# Ethernet.net
KiCad netlist of a schematic drawn in Altium Designer
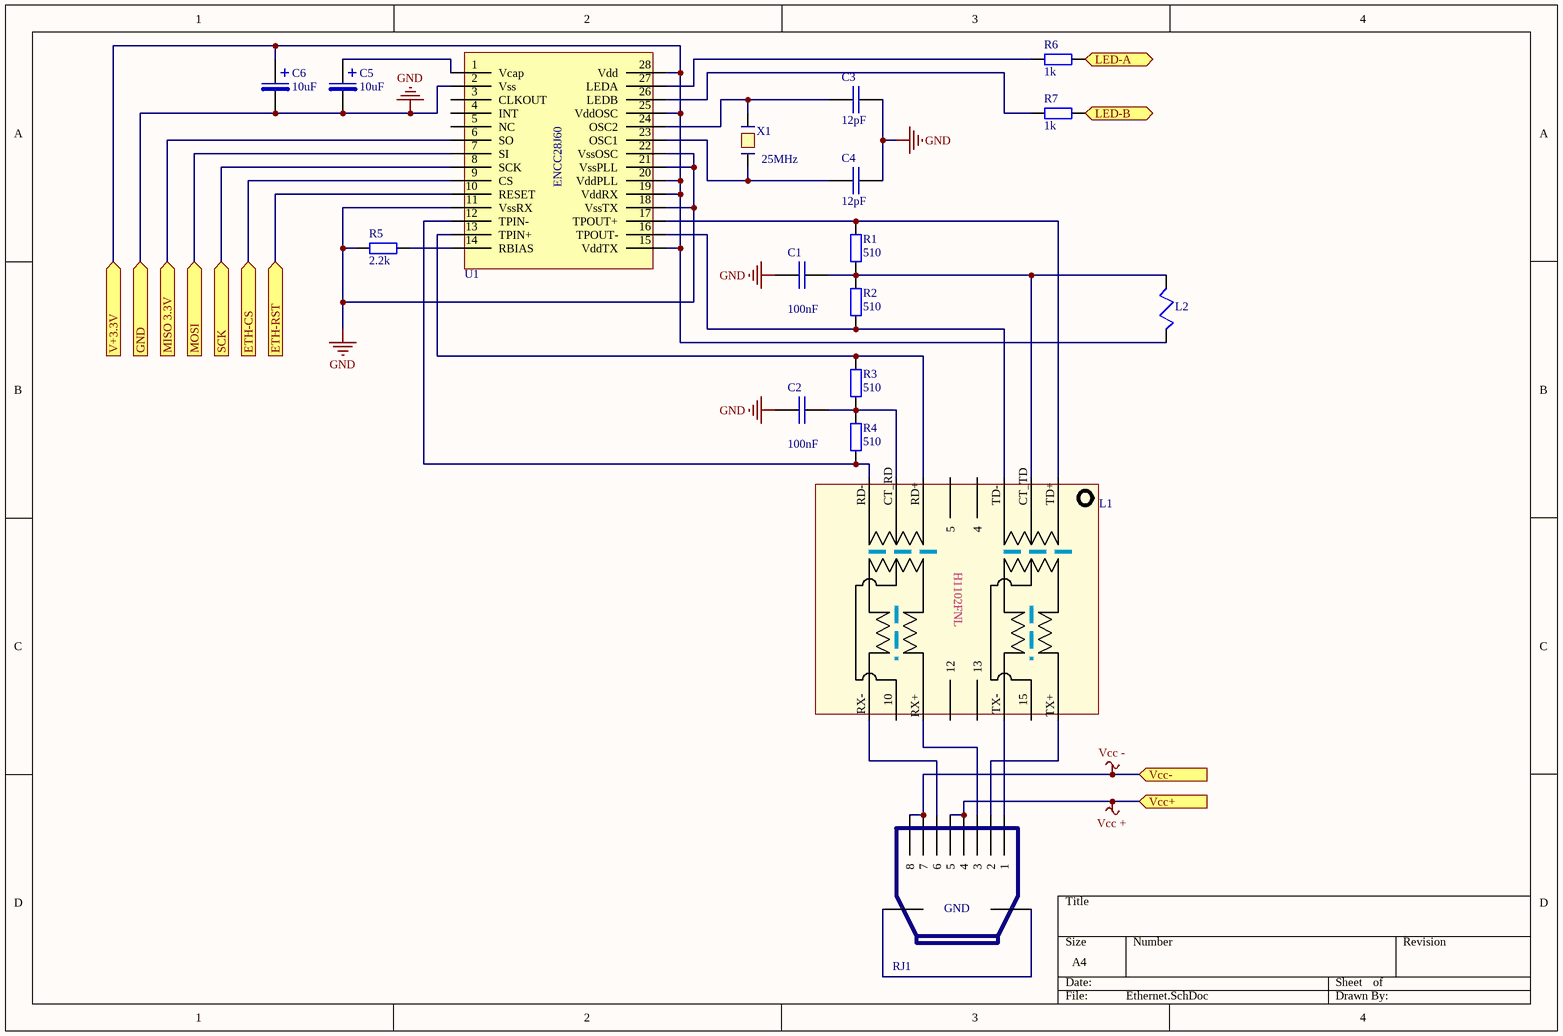
[diagram p0: Ethernet.SchDoc]

(export (version "E")
  (design (tool "Eeschema 10.0.6"))
  (components
    (comp (ref "C1")
      (value "100nF")
      (footprint "SMD-0805")
      (description "Condensator: ceramic; 100nF; 50V; X7R; ±10%; SMD; 0805; -55÷125°C")
      (libsource (lib "GenericComponents") (part "C-100nF-0805"))
    )
    (comp (ref "C2")
      (value "100nF")
      (footprint "SMD-0805")
      (description "Condensator: ceramic; 100nF; 50V; X7R; ±10%; SMD; 0805; -55÷125°C")
      (libsource (lib "GenericComponents") (part "C-100nF-0805"))
    )
    (comp (ref "C3")
      (value "12pF")
      (footprint "SMD-0805")
      (description "Condensator: ceramic; MLCC; 12pF; 50V; C0G; ±5%; SMD; 0805")
      (libsource (lib "GenericComponents") (part "C-12pF-0805"))
    )
    (comp (ref "C4")
      (value "12pF")
      (footprint "SMD-0805")
      (description "Condensator: ceramic; MLCC; 12pF; 50V; C0G; ±5%; SMD; 0805")
      (libsource (lib "GenericComponents") (part "C-12pF-0805"))
    )
    (comp (ref "C5")
      (value "10uF")
      (footprint "SMD-0805")
      (description "Condensator: ceramic; 10uF; 16V; X5R; ±10%; SMD; 0805; -55÷125°C")
      (libsource (lib "GenericComponents") (part "C-10uF-0805"))
    )
    (comp (ref "C6")
      (value "10uF")
      (footprint "SMD-0805")
      (description "Condensator: ceramic; 10uF; 16V; X5R; ±10%; SMD; 0805; -55÷125°C")
      (libsource (lib "GenericComponents") (part "C-10uF-0805"))
    )
    (comp (ref "L1")
      (value "PULSE H1102FNL")
      (footprint "H1102FNL")
      (description "Transformer: Ethernet; SMD; Trans: RX 1:1,TX 1:1; -1.1dB; 0÷70°C")
      (libsource (lib "GenericComponents") (part "PULSE H1102FNL"))
    )
    (comp (ref "L2")
      (value "FB 200mA")
      (footprint "SMD-0805")
      (description "Ferrite: bead; 150ohm; Mounting: SMD; 200mA; Case:0805; -55÷125°C")
      (libsource (lib "GenericComponents") (part "FB 200mA"))
    )
    (comp (ref "R1")
      (value "510")
      (footprint "SMD-0805")
      (description "Rezistor: thick film; SMD; 0805; 510O; 125mW; ±1%; -55÷155°C")
      (libsource (lib "GenericComponents") (part "R-510-0805"))
    )
    (comp (ref "R2")
      (value "510")
      (footprint "SMD-0805")
      (description "Rezistor: thick film; SMD; 0805; 510O; 125mW; ±1%; -55÷155°C")
      (libsource (lib "GenericComponents") (part "R-510-0805"))
    )
    (comp (ref "R3")
      (value "510")
      (footprint "SMD-0805")
      (description "Rezistor: thick film; SMD; 0805; 510O; 125mW; ±1%; -55÷155°C")
      (libsource (lib "GenericComponents") (part "R-510-0805"))
    )
    (comp (ref "R4")
      (value "510")
      (footprint "SMD-0805")
      (description "Rezistor: thick film; SMD; 0805; 510O; 125mW; ±1%; -55÷155°C")
      (libsource (lib "GenericComponents") (part "R-510-0805"))
    )
    (comp (ref "R5")
      (value "2.2k")
      (footprint "SMD-0805")
      (description "Rezistor: thick film; SMD; 0805; 2,2kO; 0,125W; ±1%; -55÷155°C")
      (fields (field (name "Comment") "20K"))
      (libsource (lib "GenericComponents") (part "R-2.2K-0805"))
    )
    (comp (ref "R6")
      (value "1k")
      (footprint "SMD-0805")
      (description "Rezistor: thick film; SMD; 0805; 1kO; 0,125W; ±5%; -55÷155°C")
      (fields (field (name "Comment") "1K"))
      (libsource (lib "GenericComponents") (part "R-1K-0805"))
    )
    (comp (ref "R7")
      (value "1k")
      (footprint "SMD-0805")
      (description "Rezistor: thick film; SMD; 0805; 1kO; 0,125W; ±5%; -55÷155°C")
      (fields (field (name "Comment") "1K"))
      (libsource (lib "GenericComponents") (part "R-1K-0805"))
    )
    (comp (ref "RJ1")
      (value "RJ45GE")
      (footprint "RJ45GE")
      (description "Soclu; RJ45; PIN:8; ecranat; Dispunere pini:8p8c; THT")
      (libsource (lib "GenericComponents") (part "RJ45GE"))
    )
    (comp (ref "U1")
      (value "ENC28J60-I/SO")
      (footprint "SO-28")
      (description "Controler Ethernet; 10Base-T; SPI; SO28; 3,1÷3,6V")
      (libsource (lib "GenericComponents") (part "ENC28J60-I/SO"))
    )
    (comp (ref "X1")
      (value "25MHz")
      (footprint "THT2-488")
      (description "Rezonator: de cuart; 25MHz; THT")
      (libsource (lib "GenericComponents") (part "YIC 25.00M-HC49-S"))
    )
  )
  (nets
    (net (code "1") (name "/ETH-CS") (class "Default")
      (node (ref "U1") (pin "9") (pinfunction "CS_9") (pintype "passive"))
    )
    (net (code "2") (name "/ETH-RST") (class "Default")
      (node (ref "U1") (pin "10") (pinfunction "RESET_10") (pintype "passive"))
    )
    (net (code "3") (name "/LED-A") (class "Default")
      (node (ref "R6") (pin "1") (pinfunction "1_1") (pintype "passive"))
    )
    (net (code "4") (name "/LED-B") (class "Default")
      (node (ref "R7") (pin "1") (pinfunction "1_1") (pintype "passive"))
    )
    (net (code "5") (name "/MISO 3.3V") (class "Default")
      (node (ref "U1") (pin "6") (pinfunction "SO_6") (pintype "passive"))
    )
    (net (code "6") (name "/MOSI") (class "Default")
      (node (ref "U1") (pin "7") (pinfunction "SI_7") (pintype "passive"))
    )
    (net (code "7") (name "/SCK") (class "Default")
      (node (ref "U1") (pin "8") (pinfunction "SCK_8") (pintype "passive"))
    )
    (net (code "8") (name "/V+3.3V") (class "Default")
      (node (ref "C6") (pin "2") (pinfunction "2_2") (pintype "passive"))
      (node (ref "L2") (pin "1") (pinfunction "1_1") (pintype "passive"))
      (node (ref "U1") (pin "15") (pinfunction "VddTX_15") (pintype "passive"))
      (node (ref "U1") (pin "19") (pinfunction "VddRX_19") (pintype "passive"))
      (node (ref "U1") (pin "20") (pinfunction "VddPLL_20") (pintype "passive"))
      (node (ref "U1") (pin "25") (pinfunction "VddOSC_25") (pintype "passive"))
      (node (ref "U1") (pin "28") (pinfunction "Vdd_28") (pintype "passive"))
    )
    (net (code "9") (name "GND") (class "Default")
      (node (ref "C1") (pin "2") (pinfunction "2_2") (pintype "passive"))
      (node (ref "C2") (pin "2") (pinfunction "2_2") (pintype "passive"))
      (node (ref "C3") (pin "1") (pinfunction "1_1") (pintype "passive"))
      (node (ref "C4") (pin "1") (pinfunction "1_1") (pintype "passive"))
      (node (ref "C5") (pin "1") (pinfunction "1_1") (pintype "passive"))
      (node (ref "C6") (pin "1") (pinfunction "1_1") (pintype "passive"))
      (node (ref "R5") (pin "2") (pinfunction "2_2") (pintype "passive"))
      (node (ref "U1") (pin "11") (pinfunction "VssRX_11") (pintype "passive"))
      (node (ref "U1") (pin "18") (pinfunction "VssTX_18") (pintype "passive"))
      (node (ref "U1") (pin "2") (pinfunction "Vss_2") (pintype "passive"))
      (node (ref "U1") (pin "21") (pinfunction "VssPLL_21") (pintype "passive"))
      (node (ref "U1") (pin "22") (pinfunction "VssOSC_22") (pintype "passive"))
    )
    (net (code "10") (name "Net-(L1-1)") (class "Default")
      (node (ref "L1") (pin "TD+") (pinfunction "1_TD+") (pintype "passive"))
      (node (ref "R1") (pin "1") (pinfunction "1_1") (pintype "passive"))
      (node (ref "U1") (pin "17") (pinfunction "TPOUT+_17") (pintype "passive"))
    )
    (net (code "11") (name "Net-(L1-2)") (class "Default")
      (node (ref "C1") (pin "1") (pinfunction "1_1") (pintype "passive"))
      (node (ref "L1") (pin "CT_TD") (pinfunction "2_CT_TD") (pintype "passive"))
      (node (ref "L2") (pin "2") (pinfunction "2_2") (pintype "passive"))
      (node (ref "R1") (pin "2") (pinfunction "2_2") (pintype "passive"))
      (node (ref "R2") (pin "1") (pinfunction "1_1") (pintype "passive"))
    )
    (net (code "12") (name "Net-(L1-3)") (class "Default")
      (node (ref "L1") (pin "TD-") (pinfunction "3_TD-") (pintype "passive"))
      (node (ref "R2") (pin "2") (pinfunction "2_2") (pintype "passive"))
      (node (ref "U1") (pin "16") (pinfunction "TPOUT-_16") (pintype "passive"))
    )
    (net (code "13") (name "Net-(L1-6)") (class "Default")
      (node (ref "L1") (pin "RD+") (pinfunction "6_RD+") (pintype "passive"))
      (node (ref "R3") (pin "1") (pinfunction "1_1") (pintype "passive"))
      (node (ref "U1") (pin "13") (pinfunction "TPIN+_13") (pintype "passive"))
    )
    (net (code "14") (name "Net-(L1-7)") (class "Default")
      (node (ref "C2") (pin "1") (pinfunction "1_1") (pintype "passive"))
      (node (ref "L1") (pin "CT_RD") (pinfunction "7_CT_RD") (pintype "passive"))
      (node (ref "R3") (pin "2") (pinfunction "2_2") (pintype "passive"))
      (node (ref "R4") (pin "1") (pinfunction "1_1") (pintype "passive"))
    )
    (net (code "15") (name "Net-(L1-8)") (class "Default")
      (node (ref "L1") (pin "RD-") (pinfunction "8_RD-") (pintype "passive"))
      (node (ref "R4") (pin "2") (pinfunction "2_2") (pintype "passive"))
      (node (ref "U1") (pin "12") (pinfunction "TPIN-_12") (pintype "passive"))
    )
    (net (code "16") (name "Net-(L1-9)") (class "Default")
      (node (ref "L1") (pin "RX-") (pinfunction "9_RX-") (pintype "passive"))
      (node (ref "RJ1") (pin "6") (pinfunction "6_6") (pintype "passive"))
    )
    (net (code "17") (name "Net-(L1-11)") (class "Default")
      (node (ref "L1") (pin "RX+") (pinfunction "11_RX+") (pintype "passive"))
      (node (ref "RJ1") (pin "3") (pinfunction "3_3") (pintype "passive"))
    )
    (net (code "18") (name "Net-(L1-14)") (class "Default")
      (node (ref "L1") (pin "TX-") (pinfunction "14_TX-") (pintype "passive"))
      (node (ref "RJ1") (pin "1") (pinfunction "1_1") (pintype "passive"))
    )
    (net (code "19") (name "Net-(L1-16)") (class "Default")
      (node (ref "L1") (pin "TX+") (pinfunction "16_TX+") (pintype "passive"))
      (node (ref "RJ1") (pin "2") (pinfunction "2_2") (pintype "passive"))
    )
    (net (code "20") (name "Net-(RJ1-10)") (class "Default")
      (node (ref "RJ1") (pin "GND-1") (pinfunction "9_GND-1") (pintype "passive"))
      (node (ref "RJ1") (pin "GND-2") (pinfunction "10_GND-2") (pintype "passive"))
    )
    (net (code "21") (name "Net-(U1-LEDA)") (class "Default")
      (node (ref "R6") (pin "2") (pinfunction "2_2") (pintype "passive"))
      (node (ref "U1") (pin "27") (pinfunction "LEDA_27") (pintype "passive"))
    )
    (net (code "22") (name "Net-(U1-LEDB)") (class "Default")
      (node (ref "R7") (pin "2") (pinfunction "2_2") (pintype "passive"))
      (node (ref "U1") (pin "26") (pinfunction "LEDB_26") (pintype "passive"))
    )
    (net (code "23") (name "Net-(U1-OSC1)") (class "Default")
      (node (ref "C4") (pin "2") (pinfunction "2_2") (pintype "passive"))
      (node (ref "U1") (pin "23") (pinfunction "OSC1_23") (pintype "passive"))
      (node (ref "X1") (pin "2") (pinfunction "A_2") (pintype "passive"))
    )
    (net (code "24") (name "Net-(U1-OSC2)") (class "Default")
      (node (ref "C3") (pin "2") (pinfunction "2_2") (pintype "passive"))
      (node (ref "U1") (pin "24") (pinfunction "OSC2_24") (pintype "passive"))
      (node (ref "X1") (pin "1") (pinfunction "C_1") (pintype "passive"))
    )
    (net (code "25") (name "Net-(U1-RBIAS)") (class "Default")
      (node (ref "R5") (pin "1") (pinfunction "1_1") (pintype "passive"))
      (node (ref "U1") (pin "14") (pinfunction "RBIAS_14") (pintype "passive"))
    )
    (net (code "26") (name "Net-(U1-Vcap)") (class "Default")
      (node (ref "C5") (pin "2") (pinfunction "2_2") (pintype "passive"))
      (node (ref "U1") (pin "1") (pinfunction "Vcap_1") (pintype "passive"))
    )
    (net (code "27") (name "Vcc +") (class "Default")
      (node (ref "RJ1") (pin "4") (pinfunction "4_4") (pintype "passive"))
      (node (ref "RJ1") (pin "5") (pinfunction "5_5") (pintype "passive"))
    )
    (net (code "28") (name "Vcc -") (class "Default")
      (node (ref "RJ1") (pin "7") (pinfunction "7_7") (pintype "passive"))
      (node (ref "RJ1") (pin "8") (pinfunction "8_8") (pintype "passive"))
    )
    (net (code "29") (name "unconnected-(L1-Pad4)") (class "Default")
      (node (ref "L1") (pin "4") (pinfunction "4_4") (pintype "passive"))
    )
    (net (code "30") (name "unconnected-(L1-Pad5)") (class "Default")
      (node (ref "L1") (pin "5") (pinfunction "5_5") (pintype "passive"))
    )
    (net (code "31") (name "unconnected-(L1-Pad10)") (class "Default")
      (node (ref "L1") (pin "10") (pinfunction "10_10") (pintype "passive"))
    )
    (net (code "32") (name "unconnected-(L1-Pad12)") (class "Default")
      (node (ref "L1") (pin "12") (pinfunction "12_12") (pintype "passive"))
    )
    (net (code "33") (name "unconnected-(L1-Pad13)") (class "Default")
      (node (ref "L1") (pin "13") (pinfunction "13_13") (pintype "passive"))
    )
    (net (code "34") (name "unconnected-(L1-Pad15)") (class "Default")
      (node (ref "L1") (pin "15") (pinfunction "15_15") (pintype "passive"))
    )
    (net (code "35") (name "unconnected-(U1-CLKOUT-Pad3)") (class "Default")
      (node (ref "U1") (pin "3") (pinfunction "CLKOUT_3") (pintype "passive"))
    )
    (net (code "36") (name "unconnected-(U1-INT-Pad4)") (class "Default")
      (node (ref "U1") (pin "4") (pinfunction "INT_4") (pintype "passive"))
    )
    (net (code "37") (name "unconnected-(U1-NC-Pad5)") (class "Default")
      (node (ref "U1") (pin "5") (pinfunction "NC_5") (pintype "passive"))
    )
  )
)
